# door_light.net
KiCad netlist of a schematic drawn in EAGLE
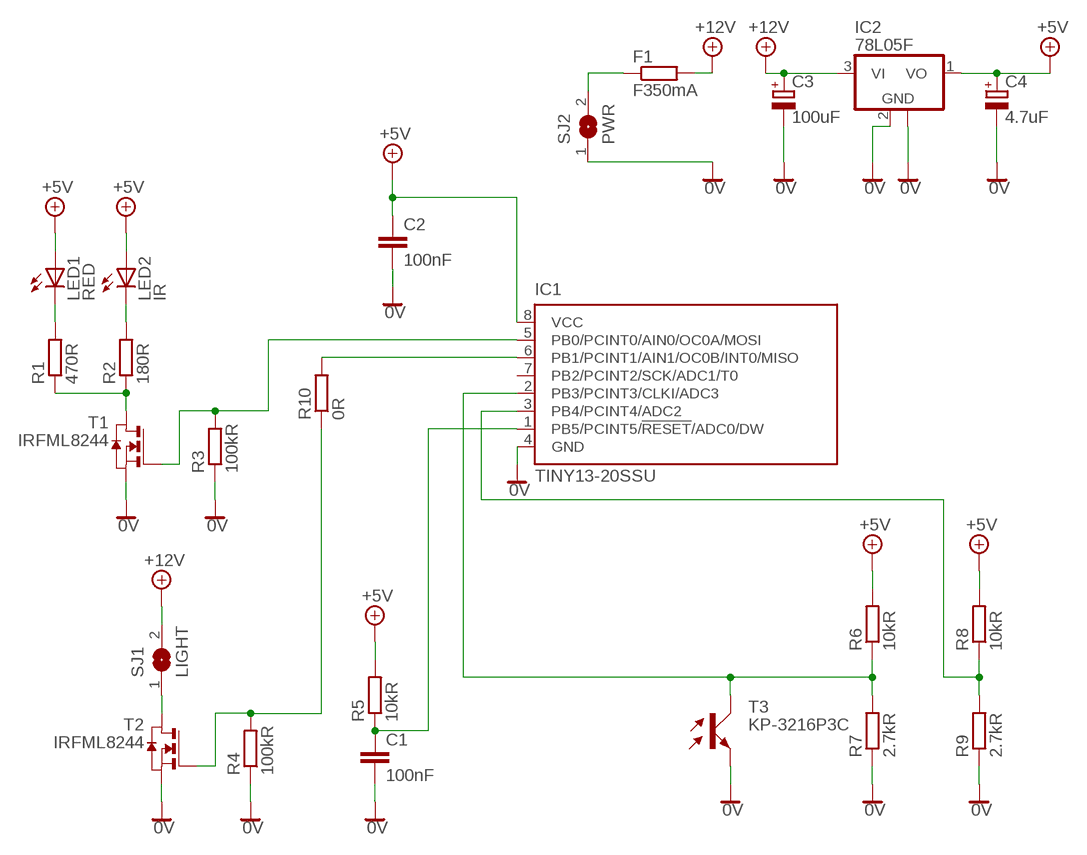
[diagram p0: schematic, sheet 1]

(export (version "E")
  (design (tool "Eeschema 10.0.6"))
  (components
    (comp (ref "C1")
      (value "100nF")
      (footprint "eagle-import:C1206")
      (libsource (lib "eagle-import") (part "C-EUC1206"))
    )
    (comp (ref "C2")
      (value "100nF")
      (footprint "eagle-import:C1206")
      (libsource (lib "eagle-import") (part "C-EUC1206"))
    )
    (comp (ref "C3")
      (value "100uF")
      (footprint "eagle-import:153CLV-0810")
      (libsource (lib "eagle-import") (part "CPOL-EU153CLV-0810"))
    )
    (comp (ref "C4")
      (value "4.7uF")
      (footprint "eagle-import:153CLV-0405")
      (libsource (lib "eagle-import") (part "CPOL-EU153CLV-0405"))
    )
    (comp (ref "F1")
      (value "F350mA")
      (footprint "eagle-import:MINI_MELF-0204W")
      (libsource (lib "eagle-import") (part "R-EU_MELF0204W"))
    )
    (comp (ref "IC1")
      (value "TINY13-20SSU")
      (footprint "eagle-import:8S1")
      (fields (field (name "MPN") "ATTINY13-20SSU"))
      (libsource (lib "eagle-import") (part "TINY13SSU-20"))
    )
    (comp (ref "IC2")
      (value "78L05F")
      (footprint "eagle-import:SOT89")
      (libsource (lib "eagle-import") (part "78LF05"))
    )
    (comp (ref "LED1")
      (value "RED")
      (footprint "eagle-import:CHIPLED_0603")
      (libsource (lib "eagle-import") (part "LEDCHIPLED_0603"))
    )
    (comp (ref "LED2")
      (value "IR")
      (footprint "eagle-import:CHIPLED_1206")
      (libsource (lib "eagle-import") (part "LEDCHIPLED_1206"))
    )
    (comp (ref "R1")
      (value "470R")
      (footprint "eagle-import:R0603")
      (libsource (lib "eagle-import") (part "R-EU_R0603"))
    )
    (comp (ref "R2")
      (value "180R")
      (footprint "eagle-import:R0603")
      (libsource (lib "eagle-import") (part "R-EU_R0603"))
    )
    (comp (ref "R3")
      (value "100kR")
      (footprint "eagle-import:R0603")
      (libsource (lib "eagle-import") (part "R-EU_R0603"))
    )
    (comp (ref "R4")
      (value "100kR")
      (footprint "eagle-import:R0603")
      (libsource (lib "eagle-import") (part "R-EU_R0603"))
    )
    (comp (ref "R5")
      (value "10kR")
      (footprint "eagle-import:R0603")
      (libsource (lib "eagle-import") (part "R-EU_R0603"))
    )
    (comp (ref "R6")
      (value "10kR")
      (footprint "eagle-import:R0603")
      (libsource (lib "eagle-import") (part "R-EU_R0603"))
    )
    (comp (ref "R7")
      (value "2.7kR")
      (footprint "eagle-import:R0603")
      (libsource (lib "eagle-import") (part "R-EU_R0603"))
    )
    (comp (ref "R8")
      (value "10kR")
      (footprint "eagle-import:R0603")
      (libsource (lib "eagle-import") (part "R-EU_R0603"))
    )
    (comp (ref "R9")
      (value "2.7kR")
      (footprint "eagle-import:R0603")
      (libsource (lib "eagle-import") (part "R-EU_R0603"))
    )
    (comp (ref "R10")
      (value "0R")
      (footprint "eagle-import:R1206W")
      (libsource (lib "eagle-import") (part "R-EU_R1206W"))
    )
    (comp (ref "SJ1")
      (value "LIGHT")
      (footprint "eagle-import:SJW")
      (libsource (lib "eagle-import") (part "SJW"))
    )
    (comp (ref "SJ2")
      (value "PWR")
      (footprint "eagle-import:SJW")
      (libsource (lib "eagle-import") (part "SJW"))
    )
    (comp (ref "T1")
      (value "IRFML8244")
      (footprint "eagle-import:SOT-23")
      (libsource (lib "eagle-import") (part "NMOSSOT23"))
    )
    (comp (ref "T2")
      (value "IRFML8244")
      (footprint "eagle-import:SOT-23")
      (libsource (lib "eagle-import") (part "NMOSSOT23"))
    )
    (comp (ref "T3")
      (value "KP-3216P3C")
      (footprint "eagle-import:OPTO-TRANS-SIEMENS_BP103")
      (libsource (lib "eagle-import") (part "KP-3216P3C"))
    )
  )
  (nets
    (net (code "1") (name "+5V") (class "Default")
      (node (ref "C2") (pin "1") (pinfunction "1_1") (pintype "passive"))
      (node (ref "C4") (pin "+") (pinfunction "+_+") (pintype "passive"))
      (node (ref "IC1") (pin "8") (pinfunction "VCC_8") (pintype "power_in"))
      (node (ref "IC2") (pin "1") (pinfunction "VO_1") (pintype "passive"))
      (node (ref "LED1") (pin "A") (pinfunction "A_A") (pintype "passive"))
      (node (ref "LED2") (pin "A") (pinfunction "A_A") (pintype "passive"))
      (node (ref "R5") (pin "2") (pinfunction "2_2") (pintype "passive"))
      (node (ref "R6") (pin "2") (pinfunction "2_2") (pintype "passive"))
      (node (ref "R8") (pin "2") (pinfunction "2_2") (pintype "passive"))
    )
    (net (code "2") (name "+12V") (class "Default")
      (node (ref "C3") (pin "+") (pinfunction "+_+") (pintype "passive"))
      (node (ref "F1") (pin "2") (pinfunction "2_2") (pintype "passive"))
      (node (ref "IC2") (pin "3") (pinfunction "VI_3") (pintype "input"))
      (node (ref "SJ1") (pin "2") (pinfunction "2_2") (pintype "passive"))
    )
    (net (code "3") (name "0V") (class "Default")
      (node (ref "C1") (pin "2") (pinfunction "2_2") (pintype "passive"))
      (node (ref "C2") (pin "2") (pinfunction "2_2") (pintype "passive"))
      (node (ref "C3") (pin "-") (pinfunction "-_-") (pintype "passive"))
      (node (ref "C4") (pin "-") (pinfunction "-_-") (pintype "passive"))
      (node (ref "IC1") (pin "4") (pinfunction "GND_4") (pintype "power_in"))
      (node (ref "IC2") (pin "2") (pinfunction "GND_2") (pintype "passive"))
      (node (ref "IC2") (pin "2@1") (pinfunction "GND_2@1") (pintype "passive"))
      (node (ref "R3") (pin "1") (pinfunction "1_1") (pintype "passive"))
      (node (ref "R4") (pin "1") (pinfunction "1_1") (pintype "passive"))
      (node (ref "R7") (pin "1") (pinfunction "1_1") (pintype "passive"))
      (node (ref "R9") (pin "1") (pinfunction "1_1") (pintype "passive"))
      (node (ref "SJ2") (pin "1") (pinfunction "1_1") (pintype "passive"))
      (node (ref "T1") (pin "2") (pinfunction "S_2") (pintype "passive"))
      (node (ref "T2") (pin "2") (pinfunction "S_2") (pintype "passive"))
      (node (ref "T3") (pin "EMITER") (pinfunction "E_EMITER") (pintype "passive"))
    )
    (net (code "4") (name "Net-(F1-Pad1)") (class "Default")
      (node (ref "F1") (pin "1") (pinfunction "1_1") (pintype "passive"))
      (node (ref "SJ2") (pin "2") (pinfunction "2_2") (pintype "passive"))
    )
    (net (code "5") (name "Net-(IC1-PB0{slash}PCINT0{slash}AIN0{slash}OC0A{slash}MOSI)") (class "Default")
      (node (ref "IC1") (pin "5") (pinfunction "PB0/PCINT0/AIN0/OC0A/MOSI_5") (pintype "bidirectional"))
      (node (ref "R3") (pin "2") (pinfunction "2_2") (pintype "passive"))
      (node (ref "T1") (pin "3") (pinfunction "G_3") (pintype "passive"))
    )
    (net (code "6") (name "Net-(IC1-PB1{slash}PCINT1{slash}AIN1{slash}OC0B{slash}INT0{slash}MISO)") (class "Default")
      (node (ref "IC1") (pin "6") (pinfunction "PB1/PCINT1/AIN1/OC0B/INT0/MISO_6") (pintype "bidirectional"))
      (node (ref "R10") (pin "2") (pinfunction "2_2") (pintype "passive"))
    )
    (net (code "7") (name "Net-(IC1-PB3{slash}PCINT3{slash}CLKI{slash}ADC3)") (class "Default")
      (node (ref "IC1") (pin "2") (pinfunction "PB3/PCINT3/CLKI/ADC3_2") (pintype "bidirectional"))
      (node (ref "R6") (pin "1") (pinfunction "1_1") (pintype "passive"))
      (node (ref "R7") (pin "2") (pinfunction "2_2") (pintype "passive"))
      (node (ref "T3") (pin "COLLECTOR") (pinfunction "C_COLLECTOR") (pintype "passive"))
    )
    (net (code "8") (name "Net-(IC1-PB4{slash}PCINT4{slash}ADC2)") (class "Default")
      (node (ref "IC1") (pin "3") (pinfunction "PB4/PCINT4/ADC2_3") (pintype "bidirectional"))
      (node (ref "R8") (pin "1") (pinfunction "1_1") (pintype "passive"))
      (node (ref "R9") (pin "2") (pinfunction "2_2") (pintype "passive"))
    )
    (net (code "9") (name "Net-(IC1-PB5{slash}PCINT5{slash}~{RESET}{slash}ADC0{slash}DW)") (class "Default")
      (node (ref "C1") (pin "1") (pinfunction "1_1") (pintype "passive"))
      (node (ref "IC1") (pin "1") (pinfunction "PB5/PCINT5/~{RESET}/ADC0/DW_1") (pintype "bidirectional"))
      (node (ref "R5") (pin "1") (pinfunction "1_1") (pintype "passive"))
    )
    (net (code "10") (name "Net-(LED1-PadC)") (class "Default")
      (node (ref "LED1") (pin "C") (pinfunction "C_C") (pintype "passive"))
      (node (ref "R1") (pin "2") (pinfunction "2_2") (pintype "passive"))
    )
    (net (code "11") (name "Net-(LED2-PadC)") (class "Default")
      (node (ref "LED2") (pin "C") (pinfunction "C_C") (pintype "passive"))
      (node (ref "R2") (pin "2") (pinfunction "2_2") (pintype "passive"))
    )
    (net (code "12") (name "Net-(T1-D)") (class "Default")
      (node (ref "R1") (pin "1") (pinfunction "1_1") (pintype "passive"))
      (node (ref "R2") (pin "1") (pinfunction "1_1") (pintype "passive"))
      (node (ref "T1") (pin "1") (pinfunction "D_1") (pintype "passive"))
    )
    (net (code "13") (name "Net-(T2-D)") (class "Default")
      (node (ref "SJ1") (pin "1") (pinfunction "1_1") (pintype "passive"))
      (node (ref "T2") (pin "1") (pinfunction "D_1") (pintype "passive"))
    )
    (net (code "14") (name "Net-(T2-G)") (class "Default")
      (node (ref "R10") (pin "1") (pinfunction "1_1") (pintype "passive"))
      (node (ref "R4") (pin "2") (pinfunction "2_2") (pintype "passive"))
      (node (ref "T2") (pin "3") (pinfunction "G_3") (pintype "passive"))
    )
    (net (code "15") (name "unconnected-(IC1-PB2{slash}PCINT2{slash}SCK{slash}ADC1{slash}T0-Pad7)") (class "Default")
      (node (ref "IC1") (pin "7") (pinfunction "PB2/PCINT2/SCK/ADC1/T0_7") (pintype "bidirectional"))
    )
  )
)
